# Wash_Hand_v1_2.net
KiCad netlist of a schematic drawn in EAGLE
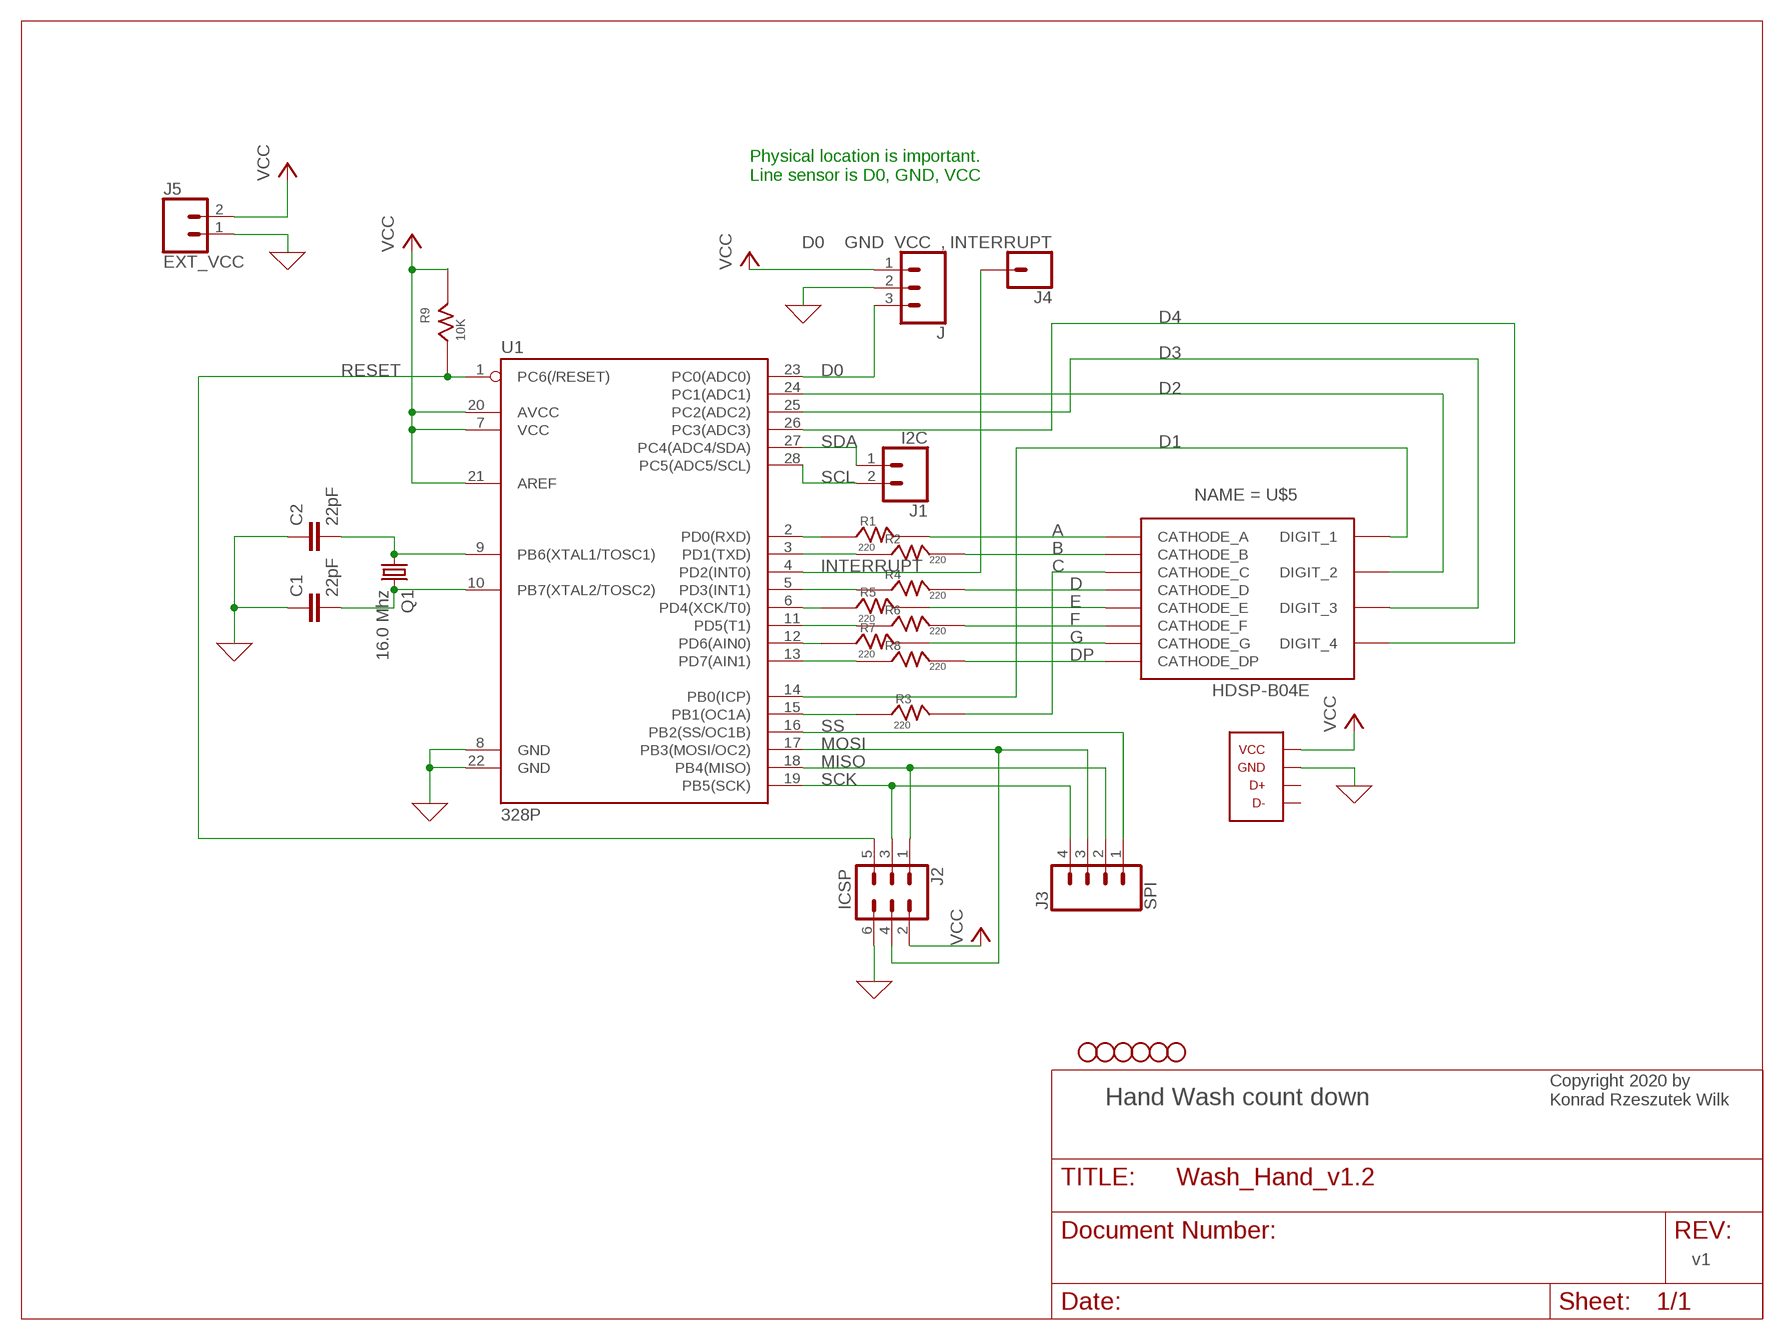
[diagram p0: schematic, sheet 1]

(export (version "E")
  (design (tool "Eeschema 10.0.6"))
  (components
    (comp (ref "C1")
      (value "22pF")
      (footprint "eagle-import:CAP-PTH-2.54")
      (libsource (lib "eagle-import") (part "22PF-PTH-2.54MM-200V-5%"))
    )
    (comp (ref "C2")
      (value "22pF")
      (footprint "eagle-import:CAP-PTH-2.54")
      (libsource (lib "eagle-import") (part "22PF-PTH-2.54MM-200V-5%"))
    )
    (comp (ref "H1")
      (value "STAND-OFF")
      (footprint "eagle-import:STAND-OFF")
      (libsource (lib "eagle-import") (part "STAND-OFF"))
    )
    (comp (ref "H2")
      (value "STAND-OFF")
      (footprint "eagle-import:STAND-OFF")
      (libsource (lib "eagle-import") (part "STAND-OFF"))
    )
    (comp (ref "H3")
      (value "STAND-OFF")
      (footprint "eagle-import:STAND-OFF")
      (libsource (lib "eagle-import") (part "STAND-OFF"))
    )
    (comp (ref "H4")
      (value "STAND-OFF")
      (footprint "eagle-import:STAND-OFF")
      (libsource (lib "eagle-import") (part "STAND-OFF"))
    )
    (comp (ref "H5")
      (value "STAND-OFF")
      (footprint "eagle-import:STAND-OFF")
      (libsource (lib "eagle-import") (part "STAND-OFF"))
    )
    (comp (ref "H6")
      (value "STAND-OFF")
      (footprint "eagle-import:STAND-OFF")
      (libsource (lib "eagle-import") (part "STAND-OFF"))
    )
    (comp (ref "J")
      (value "D0 GND VCC ,")
      (footprint "eagle-import:1X03")
      (libsource (lib "eagle-import") (part "CONN_03"))
    )
    (comp (ref "J1")
      (value "I2C")
      (footprint "eagle-import:1X02")
      (libsource (lib "eagle-import") (part "CONN_02"))
    )
    (comp (ref "J2")
      (value "ICSP")
      (footprint "eagle-import:2X3")
      (libsource (lib "eagle-import") (part "CONN_03X2FEMALE"))
    )
    (comp (ref "J3")
      (value "SPI")
      (footprint "eagle-import:1X04")
      (libsource (lib "eagle-import") (part "CONN_04"))
    )
    (comp (ref "J4")
      (value "INTERRUPT")
      (footprint "eagle-import:1X01")
      (libsource (lib "eagle-import") (part "CONN_01"))
    )
    (comp (ref "J5")
      (value "EXT_VCC")
      (footprint "eagle-import:1X02")
      (libsource (lib "eagle-import") (part "CONN_02"))
    )
    (comp (ref "Q1")
      (value "16.0 Mhz")
      (footprint "eagle-import:HC49_S")
      (libsource (lib "eagle-import") (part "CRYSTALHC49S"))
    )
    (comp (ref "R1")
      (value "220")
      (footprint "eagle-import:RESISTOR")
      (libsource (lib "eagle-import") (part "RESISTOR"))
    )
    (comp (ref "R2")
      (value "220")
      (footprint "eagle-import:RESISTOR")
      (libsource (lib "eagle-import") (part "RESISTOR"))
    )
    (comp (ref "R3")
      (value "220")
      (footprint "eagle-import:RESISTOR")
      (libsource (lib "eagle-import") (part "RESISTOR"))
    )
    (comp (ref "R4")
      (value "220")
      (footprint "eagle-import:RESISTOR")
      (libsource (lib "eagle-import") (part "RESISTOR"))
    )
    (comp (ref "R5")
      (value "220")
      (footprint "eagle-import:RESISTOR")
      (libsource (lib "eagle-import") (part "RESISTOR"))
    )
    (comp (ref "R6")
      (value "220")
      (footprint "eagle-import:RESISTOR")
      (libsource (lib "eagle-import") (part "RESISTOR"))
    )
    (comp (ref "R7")
      (value "220")
      (footprint "eagle-import:RESISTOR")
      (libsource (lib "eagle-import") (part "RESISTOR"))
    )
    (comp (ref "R8")
      (value "220")
      (footprint "eagle-import:RESISTOR")
      (libsource (lib "eagle-import") (part "RESISTOR"))
    )
    (comp (ref "R9")
      (value "10K")
      (footprint "eagle-import:RESISTOR")
      (libsource (lib "eagle-import") (part "RESISTOR"))
    )
    (comp (ref "U$4")
      (value "USB_MICROB_10118194_AMPHENOL")
      (footprint "eagle-import:USB_MICROB_10118194_AMPHENOL")
      (libsource (lib "eagle-import") (part "USB_MICROB_10118194_AMPHENOL"))
    )
    (comp (ref "U$5")
      (value "HDSP-B04E")
      (footprint "eagle-import:HDSP-B0XE")
      (libsource (lib "eagle-import") (part "HDSP-B04E"))
    )
    (comp (ref "U1")
      (value "328P")
      (footprint "eagle-import:DIP28")
      (libsource (lib "eagle-import") (part "ATMEGA328P_PDIP"))
    )
  )
  (nets
    (net (code "1") (name "/A") (class "Default")
      (node (ref "R1") (pin "R_2") (pinfunction "R_2_R_2") (pintype "bidirectional"))
      (node (ref "U$5") (pin "PIN$11") (pinfunction "CATHODE_A_PIN$11") (pintype "input"))
    )
    (net (code "2") (name "/B") (class "Default")
      (node (ref "R2") (pin "R_2") (pinfunction "R_2_R_2") (pintype "bidirectional"))
      (node (ref "U$5") (pin "PIN$7") (pinfunction "CATHODE_B_PIN$7") (pintype "input"))
    )
    (net (code "3") (name "/C") (class "Default")
      (node (ref "R3") (pin "R_2") (pinfunction "R_2_R_2") (pintype "bidirectional"))
      (node (ref "U$5") (pin "PIN$4") (pinfunction "CATHODE_C_PIN$4") (pintype "input"))
    )
    (net (code "4") (name "/D") (class "Default")
      (node (ref "R4") (pin "R_2") (pinfunction "R_2_R_2") (pintype "bidirectional"))
      (node (ref "U$5") (pin "PIN$2") (pinfunction "CATHODE_D_PIN$2") (pintype "input"))
    )
    (net (code "5") (name "/D0") (class "Default")
      (node (ref "J") (pin "3") (pinfunction "3_3") (pintype "passive"))
      (node (ref "U1") (pin "23") (pinfunction "PC0(ADC0)_23") (pintype "bidirectional"))
    )
    (net (code "6") (name "/D1") (class "Default")
      (node (ref "U$5") (pin "PIN12") (pinfunction "DIGIT_1_PIN12") (pintype "input"))
      (node (ref "U1") (pin "14") (pinfunction "PB0(ICP)_14") (pintype "bidirectional"))
    )
    (net (code "7") (name "/D2") (class "Default")
      (node (ref "U$5") (pin "PIN$9") (pinfunction "DIGIT_2_PIN$9") (pintype "input"))
      (node (ref "U1") (pin "24") (pinfunction "PC1(ADC1)_24") (pintype "bidirectional"))
    )
    (net (code "8") (name "/D3") (class "Default")
      (node (ref "U$5") (pin "PIN$8") (pinfunction "DIGIT_3_PIN$8") (pintype "input"))
      (node (ref "U1") (pin "25") (pinfunction "PC2(ADC2)_25") (pintype "bidirectional"))
    )
    (net (code "9") (name "/D4") (class "Default")
      (node (ref "U$5") (pin "PIN$6") (pinfunction "DIGIT_4_PIN$6") (pintype "input"))
      (node (ref "U1") (pin "26") (pinfunction "PC3(ADC3)_26") (pintype "bidirectional"))
    )
    (net (code "10") (name "/DP") (class "Default")
      (node (ref "R8") (pin "R_2") (pinfunction "R_2_R_2") (pintype "bidirectional"))
      (node (ref "U$5") (pin "PIN$3") (pinfunction "CATHODE_DP_PIN$3") (pintype "input"))
    )
    (net (code "11") (name "/E") (class "Default")
      (node (ref "R5") (pin "R_2") (pinfunction "R_2_R_2") (pintype "bidirectional"))
      (node (ref "U$5") (pin "PIN$1") (pinfunction "CATHODE_E_PIN$1") (pintype "input"))
    )
    (net (code "12") (name "/F") (class "Default")
      (node (ref "R6") (pin "R_2") (pinfunction "R_2_R_2") (pintype "bidirectional"))
      (node (ref "U$5") (pin "PIN$10") (pinfunction "CATHODE_F_PIN$10") (pintype "input"))
    )
    (net (code "13") (name "/G") (class "Default")
      (node (ref "R7") (pin "R_2") (pinfunction "R_2_R_2") (pintype "bidirectional"))
      (node (ref "U$5") (pin "PIN$5") (pinfunction "CATHODE_G_PIN$5") (pintype "input"))
    )
    (net (code "14") (name "/INTERRUPT") (class "Default")
      (node (ref "J4") (pin "1") (pinfunction "1_1") (pintype "passive"))
      (node (ref "U1") (pin "4") (pinfunction "PD2(INT0)_4") (pintype "bidirectional"))
    )
    (net (code "15") (name "/MISO") (class "Default")
      (node (ref "J2") (pin "1") (pinfunction "1_1") (pintype "bidirectional"))
      (node (ref "J3") (pin "2") (pinfunction "2_2") (pintype "passive"))
      (node (ref "U1") (pin "18") (pinfunction "PB4(MISO)_18") (pintype "bidirectional"))
    )
    (net (code "16") (name "/MOSI") (class "Default")
      (node (ref "J2") (pin "4") (pinfunction "4_4") (pintype "bidirectional"))
      (node (ref "J3") (pin "3") (pinfunction "3_3") (pintype "passive"))
      (node (ref "U1") (pin "17") (pinfunction "PB3(MOSI/OC2)_17") (pintype "bidirectional"))
    )
    (net (code "17") (name "/RESET") (class "Default")
      (node (ref "J2") (pin "5") (pinfunction "5_5") (pintype "bidirectional"))
      (node (ref "R9") (pin "R_1") (pinfunction "R_1_R_1") (pintype "bidirectional"))
      (node (ref "U1") (pin "1") (pinfunction "PC6(/RESET)_1") (pintype "bidirectional"))
    )
    (net (code "18") (name "/SCK") (class "Default")
      (node (ref "J2") (pin "3") (pinfunction "3_3") (pintype "bidirectional"))
      (node (ref "J3") (pin "4") (pinfunction "4_4") (pintype "passive"))
      (node (ref "U1") (pin "19") (pinfunction "PB5(SCK)_19") (pintype "bidirectional"))
    )
    (net (code "19") (name "/SCL") (class "Default")
      (node (ref "J1") (pin "2") (pinfunction "2_2") (pintype "passive"))
      (node (ref "U1") (pin "28") (pinfunction "PC5(ADC5/SCL)_28") (pintype "bidirectional"))
    )
    (net (code "20") (name "/SDA") (class "Default")
      (node (ref "J1") (pin "1") (pinfunction "1_1") (pintype "passive"))
      (node (ref "U1") (pin "27") (pinfunction "PC4(ADC4/SDA)_27") (pintype "bidirectional"))
    )
    (net (code "21") (name "/SS") (class "Default")
      (node (ref "J3") (pin "1") (pinfunction "1_1") (pintype "passive"))
      (node (ref "U1") (pin "16") (pinfunction "PB2(SS/OC1B)_16") (pintype "bidirectional"))
    )
    (net (code "22") (name "GND") (class "Default")
      (node (ref "C1") (pin "1") (pinfunction "1_1") (pintype "passive"))
      (node (ref "C2") (pin "1") (pinfunction "1_1") (pintype "passive"))
      (node (ref "J") (pin "2") (pinfunction "2_2") (pintype "passive"))
      (node (ref "J2") (pin "6") (pinfunction "6_6") (pintype "bidirectional"))
      (node (ref "J5") (pin "1") (pinfunction "1_1") (pintype "passive"))
      (node (ref "U$4") (pin "5") (pinfunction "GND_5") (pintype "bidirectional"))
      (node (ref "U1") (pin "22") (pinfunction "GND_22") (pintype "bidirectional"))
      (node (ref "U1") (pin "8") (pinfunction "GND_8") (pintype "bidirectional"))
    )
    (net (code "23") (name "Net-(U1-PB1(OC1A))") (class "Default")
      (node (ref "R3") (pin "R_1") (pinfunction "R_1_R_1") (pintype "bidirectional"))
      (node (ref "U1") (pin "15") (pinfunction "PB1(OC1A)_15") (pintype "bidirectional"))
    )
    (net (code "24") (name "Net-(U1-PB6(XTAL1{slash}TOSC1))") (class "Default")
      (node (ref "C2") (pin "2") (pinfunction "2_2") (pintype "passive"))
      (node (ref "Q1") (pin "1") (pinfunction "1_1") (pintype "passive"))
      (node (ref "U1") (pin "9") (pinfunction "PB6(XTAL1/TOSC1)_9") (pintype "bidirectional"))
    )
    (net (code "25") (name "Net-(U1-PB7(XTAL2{slash}TOSC2))") (class "Default")
      (node (ref "C1") (pin "2") (pinfunction "2_2") (pintype "passive"))
      (node (ref "Q1") (pin "2") (pinfunction "2_2") (pintype "passive"))
      (node (ref "U1") (pin "10") (pinfunction "PB7(XTAL2/TOSC2)_10") (pintype "bidirectional"))
    )
    (net (code "26") (name "Net-(U1-PD0(RXD))") (class "Default")
      (node (ref "R1") (pin "R_1") (pinfunction "R_1_R_1") (pintype "bidirectional"))
      (node (ref "U1") (pin "2") (pinfunction "PD0(RXD)_2") (pintype "bidirectional"))
    )
    (net (code "27") (name "Net-(U1-PD1(TXD))") (class "Default")
      (node (ref "R2") (pin "R_1") (pinfunction "R_1_R_1") (pintype "bidirectional"))
      (node (ref "U1") (pin "3") (pinfunction "PD1(TXD)_3") (pintype "bidirectional"))
    )
    (net (code "28") (name "Net-(U1-PD3(INT1))") (class "Default")
      (node (ref "R4") (pin "R_1") (pinfunction "R_1_R_1") (pintype "bidirectional"))
      (node (ref "U1") (pin "5") (pinfunction "PD3(INT1)_5") (pintype "bidirectional"))
    )
    (net (code "29") (name "Net-(U1-PD4(XCK{slash}T0))") (class "Default")
      (node (ref "R5") (pin "R_1") (pinfunction "R_1_R_1") (pintype "bidirectional"))
      (node (ref "U1") (pin "6") (pinfunction "PD4(XCK/T0)_6") (pintype "bidirectional"))
    )
    (net (code "30") (name "Net-(U1-PD5(T1))") (class "Default")
      (node (ref "R6") (pin "R_1") (pinfunction "R_1_R_1") (pintype "bidirectional"))
      (node (ref "U1") (pin "11") (pinfunction "PD5(T1)_11") (pintype "bidirectional"))
    )
    (net (code "31") (name "Net-(U1-PD6(AIN0))") (class "Default")
      (node (ref "R7") (pin "R_1") (pinfunction "R_1_R_1") (pintype "bidirectional"))
      (node (ref "U1") (pin "12") (pinfunction "PD6(AIN0)_12") (pintype "bidirectional"))
    )
    (net (code "32") (name "Net-(U1-PD7(AIN1))") (class "Default")
      (node (ref "R8") (pin "R_1") (pinfunction "R_1_R_1") (pintype "bidirectional"))
      (node (ref "U1") (pin "13") (pinfunction "PD7(AIN1)_13") (pintype "bidirectional"))
    )
    (net (code "33") (name "VCC") (class "Default")
      (node (ref "J") (pin "1") (pinfunction "1_1") (pintype "passive"))
      (node (ref "J2") (pin "2") (pinfunction "2_2") (pintype "bidirectional"))
      (node (ref "J5") (pin "2") (pinfunction "2_2") (pintype "passive"))
      (node (ref "R9") (pin "R_2") (pinfunction "R_2_R_2") (pintype "bidirectional"))
      (node (ref "U$4") (pin "1") (pinfunction "VCC_1") (pintype "bidirectional"))
      (node (ref "U1") (pin "20") (pinfunction "AVCC_20") (pintype "bidirectional"))
      (node (ref "U1") (pin "21") (pinfunction "AREF_21") (pintype "bidirectional"))
      (node (ref "U1") (pin "7") (pinfunction "VCC_7") (pintype "bidirectional"))
    )
    (net (code "34") (name "unconnected-(U$4-D+-Pad3)") (class "Default")
      (node (ref "U$4") (pin "3") (pinfunction "D+_3") (pintype "bidirectional"))
    )
    (net (code "35") (name "unconnected-(U$4-D--Pad2)") (class "Default")
      (node (ref "U$4") (pin "2") (pinfunction "D-_2") (pintype "bidirectional"))
    )
  )
)
